# Audio_Video_Controller.net
KiCad netlist of a schematic drawn in Altium Designer
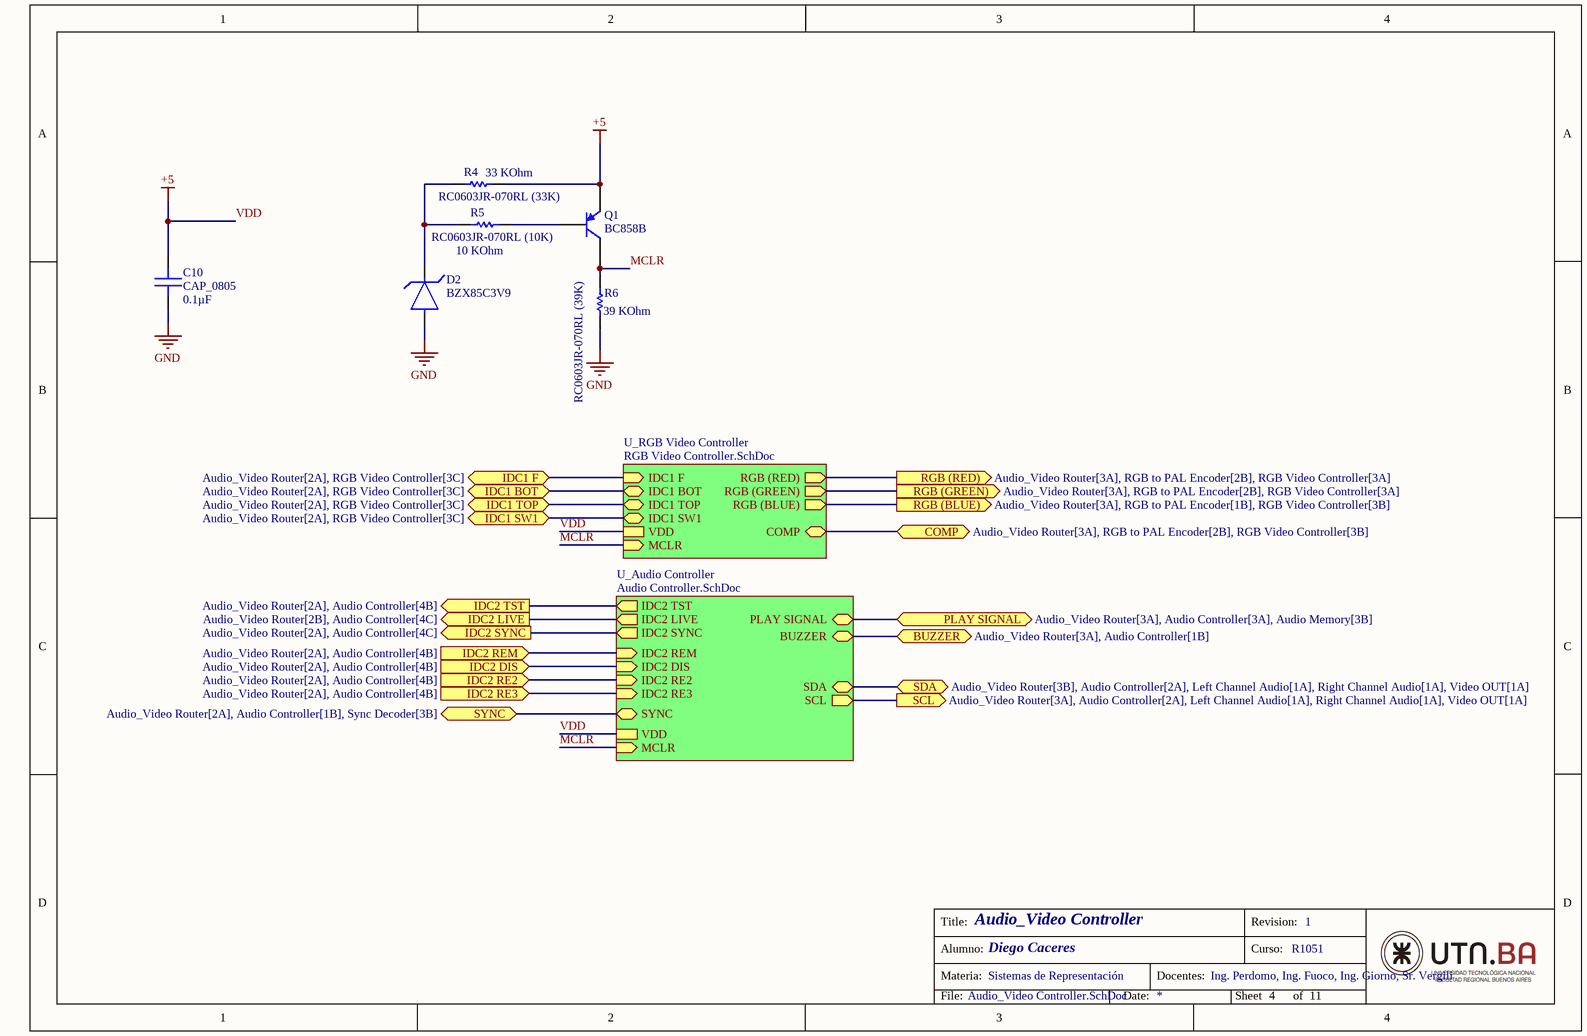
[diagram p0: Audio_Video Controller.SchDoc]

(export (version "E")
  (design (tool "Eeschema 10.0.6"))
  (components
    (comp (ref "C10")
      (value "CAP_0805")
      (footprint "0805_CAPACITOR_DCACERES")
      (description "Capacitor SMD, encapsulado 0805")
      (fields (field (name "ALTIUM_VALUE") "0.1µF"))
      (libsource (lib "PF_Schlib") (part "CAPACITOR_0805_Caceres"))
    )
    (comp (ref "D2")
      (value "BZX85C3V9")
      (footprint "AXIAL_LEAD_D0-41_BZX85C3V9_DCACERES")
      (description "Diodo Zener 3.9V, BZX85C3V9, Thru Hole")
      (fields
        (field (name "PARTNUMBER") "BZX85C3V9-TR")
        (field (name "MANUFACTURER") "Fairchild Semiconductor")
      )
      (libsource (lib "PF_Schlib") (part "BZX85C3V9_Caceres"))
    )
    (comp (ref "Q1")
      (value "BC858B")
      (footprint "INF-SOT23_M")
      (description "PNP Silicon AF Transistor, 30 V VCEO, 100 mA IC, SOT23, Reel, Green")
      (fields (field (name "MANUFACTURER") "Infineon"))
      (libsource (lib "Altium Content Vault") (part "INF-BJTPNP-BEC-3"))
    )
    (comp (ref "R4")
      (value "RC0603JR-070RL (33K)")
      (footprint "RESC1608X55X25ML10T15")
      (description "Chip Resistor, 0 Ohm, +/- 5%, 0.1 W, -55 to 155 degC, 0603 (1608 Metric), RoHS, Tape and Reel")
      (fields
        (field (name "TOLERANCE") "5%")
        (field (name "RESISTANCE") "33 KOhm")
        (field (name "MANUFACTURER") "Yageo")
      )
      (libsource (lib "Altium Content Vault") (part "RES-2"))
    )
    (comp (ref "R5")
      (value "RC0603JR-070RL (10K)")
      (footprint "RESC1608X55X25ML10T15")
      (description "Chip Resistor, 0 Ohm, +/- 5%, 0.1 W, -55 to 155 degC, 0603 (1608 Metric), RoHS, Tape and Reel")
      (fields
        (field (name "TOLERANCE") "5%")
        (field (name "RESISTANCE") "10 KOhm")
        (field (name "MANUFACTURER") "Yageo")
      )
      (libsource (lib "Altium Content Vault") (part "RES-2"))
    )
    (comp (ref "R6")
      (value "RC0603JR-070RL (39K)")
      (footprint "RESC1608X55X25ML10T15")
      (description "Chip Resistor, 0 Ohm, +/- 5%, 0.1 W, -55 to 155 degC, 0603 (1608 Metric), RoHS, Tape and Reel")
      (fields
        (field (name "TOLERANCE") "5%")
        (field (name "RESISTANCE") "39 KOhm")
        (field (name "MANUFACTURER") "Yageo")
      )
      (libsource (lib "Altium Content Vault") (part "RES-2"))
    )
  )
  (nets
    (net (code "1") (name "+5") (class "Default")
      (node (ref "C10") (pin "2") (pinfunction "2_2") (pintype "passive"))
      (node (ref "Q1") (pin "2") (pinfunction "E_2") (pintype "passive"))
      (node (ref "R4") (pin "1") (pinfunction "1_1") (pintype "passive"))
    )
    (net (code "15") (name "/MCLR") (class "Default")
      (node (ref "Q1") (pin "3") (pinfunction "C_3") (pintype "passive"))
      (node (ref "R6") (pin "1") (pinfunction "1_1") (pintype "passive"))
    )
    (net (code "23") (name "GND") (class "Default")
      (node (ref "C10") (pin "1") (pinfunction "1_1") (pintype "passive"))
      (node (ref "D2") (pin "1") (pinfunction "1_1") (pintype "passive"))
      (node (ref "R6") (pin "2") (pinfunction "2_2") (pintype "passive"))
    )
    (net (code "24") (name "Net-(D2-Pad2)") (class "Default")
      (node (ref "D2") (pin "2") (pinfunction "2_2") (pintype "passive"))
      (node (ref "R4") (pin "2") (pinfunction "2_2") (pintype "passive"))
      (node (ref "R5") (pin "2") (pinfunction "2_2") (pintype "passive"))
    )
    (net (code "25") (name "Net-(Q1-B)") (class "Default")
      (node (ref "Q1") (pin "1") (pinfunction "B_1") (pintype "passive"))
      (node (ref "R5") (pin "1") (pinfunction "1_1") (pintype "passive"))
    )
  )
)
